# MPR.net
KiCad netlist of a schematic drawn in Altium Designer
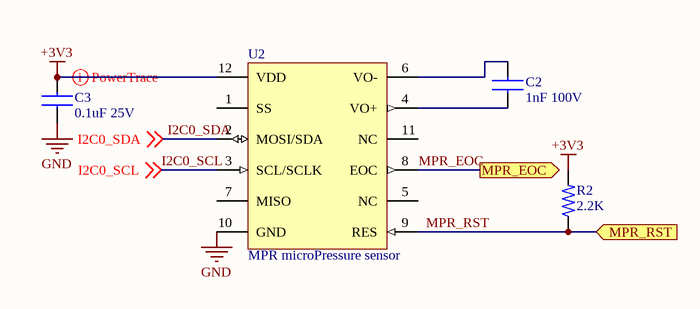
[diagram p0: MPR.SchDoc]

(export (version "E")
  (design (tool "Eeschema 10.0.6"))
  (components
    (comp (ref "C2")
      (value "1nF 100V")
      (footprint "Chip2Pin_1.6x0.8x0.9_CAP")
      (description "0603 1 nF 100V ±10% Tol. X7R Surface Mount Multilayer Ceramic Capacitor")
      (fields
        (field (name "MANUFACTURER") "Murata")
        (field (name "MANUFACTURER PART NUMBER") "GRM188R72A102KA01D")
      )
      (libsource (lib "LPEDT_Parts") (part "GRM188R72A102KA01D"))
    )
    (comp (ref "C3")
      (value "0.1uF 25V")
      (footprint "Chip2Pin_1.6x0.8x0.9_CAP")
      (description "Cap Ceramic 0.1uF 25V X7R 10% Pad SMD 0603 Soft Termination 125C Automotive T/R")
      (fields
        (field (name "MANUFACTURER") "Murata")
        (field (name "MANUFACTURER PART NUMBER") "GCJ188R71E104KA12D")
      )
      (libsource (lib "LPEDT_Parts") (part "GCJ188R71E104KA12D"))
    )
    (comp (ref "R2")
      (value "2.2K")
      (footprint "RES_0603_1608X06")
      (description "Res Thick Film 0603 2.2K Ohm 1% 0.1W(1/10W) ±100ppm/°C Pad SMD T/R")
      (fields
        (field (name "MANUFACTURER") "Yageo")
        (field (name "MANUFACTURER PART NUMBER") "RC0603FR-072K2L")
      )
      (libsource (lib "LPEDT_Parts") (part "RC0603FR-072K2L"))
    )
    (comp (ref "U2")
      (value "MPR microPressure sensor")
      (footprint "12-MANUAL-5x5")
      (description "Board Mount Pressure Sensor 0psi to 25psi Absolute 12-Pin T/R")
      (fields
        (field (name "MANUFACTURER") "Honeywell")
        (field (name "MANUFACTURER PART NUMBER") "MPRLS0025PA00001A")
      )
      (libsource (lib "LPEDT_Parts") (part "MPRLS0025PA00001A"))
    )
  )
  (nets
    (net (code "1") (name "+3V3") (class "Default")
      (node (ref "C3") (pin "1") (pinfunction "1_1") (pintype "passive"))
      (node (ref "R2") (pin "2") (pinfunction "2_2") (pintype "passive"))
      (node (ref "U2") (pin "12") (pinfunction "VDD_12") (pintype "power_in"))
    )
    (net (code "2") (name "/MPR_EOC") (class "Default")
      (node (ref "U2") (pin "8") (pinfunction "EOC_8") (pintype "output"))
    )
    (net (code "3") (name "/MPR_RST") (class "Default")
      (node (ref "R2") (pin "1") (pinfunction "1_1") (pintype "passive"))
      (node (ref "U2") (pin "9") (pinfunction "RES_9") (pintype "input"))
    )
    (net (code "4") (name "GND") (class "Default")
      (node (ref "C3") (pin "2") (pinfunction "2_2") (pintype "passive"))
      (node (ref "U2") (pin "10") (pinfunction "GND_10") (pintype "passive"))
    )
    (net (code "5") (name "I2C0_SCL") (class "Default")
      (node (ref "U2") (pin "3") (pinfunction "SCL/SCLK_3") (pintype "input"))
    )
    (net (code "6") (name "I2C0_SDA") (class "Default")
      (node (ref "U2") (pin "2") (pinfunction "MOSI/SDA_2") (pintype "bidirectional"))
    )
    (net (code "7") (name "Net-(U2-VO+)") (class "Default")
      (node (ref "C2") (pin "2") (pinfunction "2_2") (pintype "passive"))
      (node (ref "U2") (pin "4") (pinfunction "VO+_4") (pintype "output"))
    )
    (net (code "8") (name "Net-(U2-VO-)") (class "Default")
      (node (ref "C2") (pin "1") (pinfunction "1_1") (pintype "passive"))
      (node (ref "U2") (pin "6") (pinfunction "VO-_6") (pintype "power_in"))
    )
    (net (code "9") (name "unconnected-(U2-MISO-Pad7)") (class "Default")
      (node (ref "U2") (pin "7") (pinfunction "MISO_7") (pintype "tri_state"))
    )
    (net (code "10") (name "unconnected-(U2-NC-Pad5)") (class "Default")
      (node (ref "U2") (pin "5") (pinfunction "NC_5") (pintype "tri_state"))
    )
    (net (code "11") (name "unconnected-(U2-NC-Pad11)") (class "Default")
      (node (ref "U2") (pin "11") (pinfunction "NC_11") (pintype "tri_state"))
    )
    (net (code "12") (name "unconnected-(U2-SS-Pad1)") (class "Default")
      (node (ref "U2") (pin "1") (pinfunction "SS_1") (pintype "tri_state"))
    )
  )
)
